# EKG_Modul_II.net
KiCad netlist of a schematic drawn in EAGLE
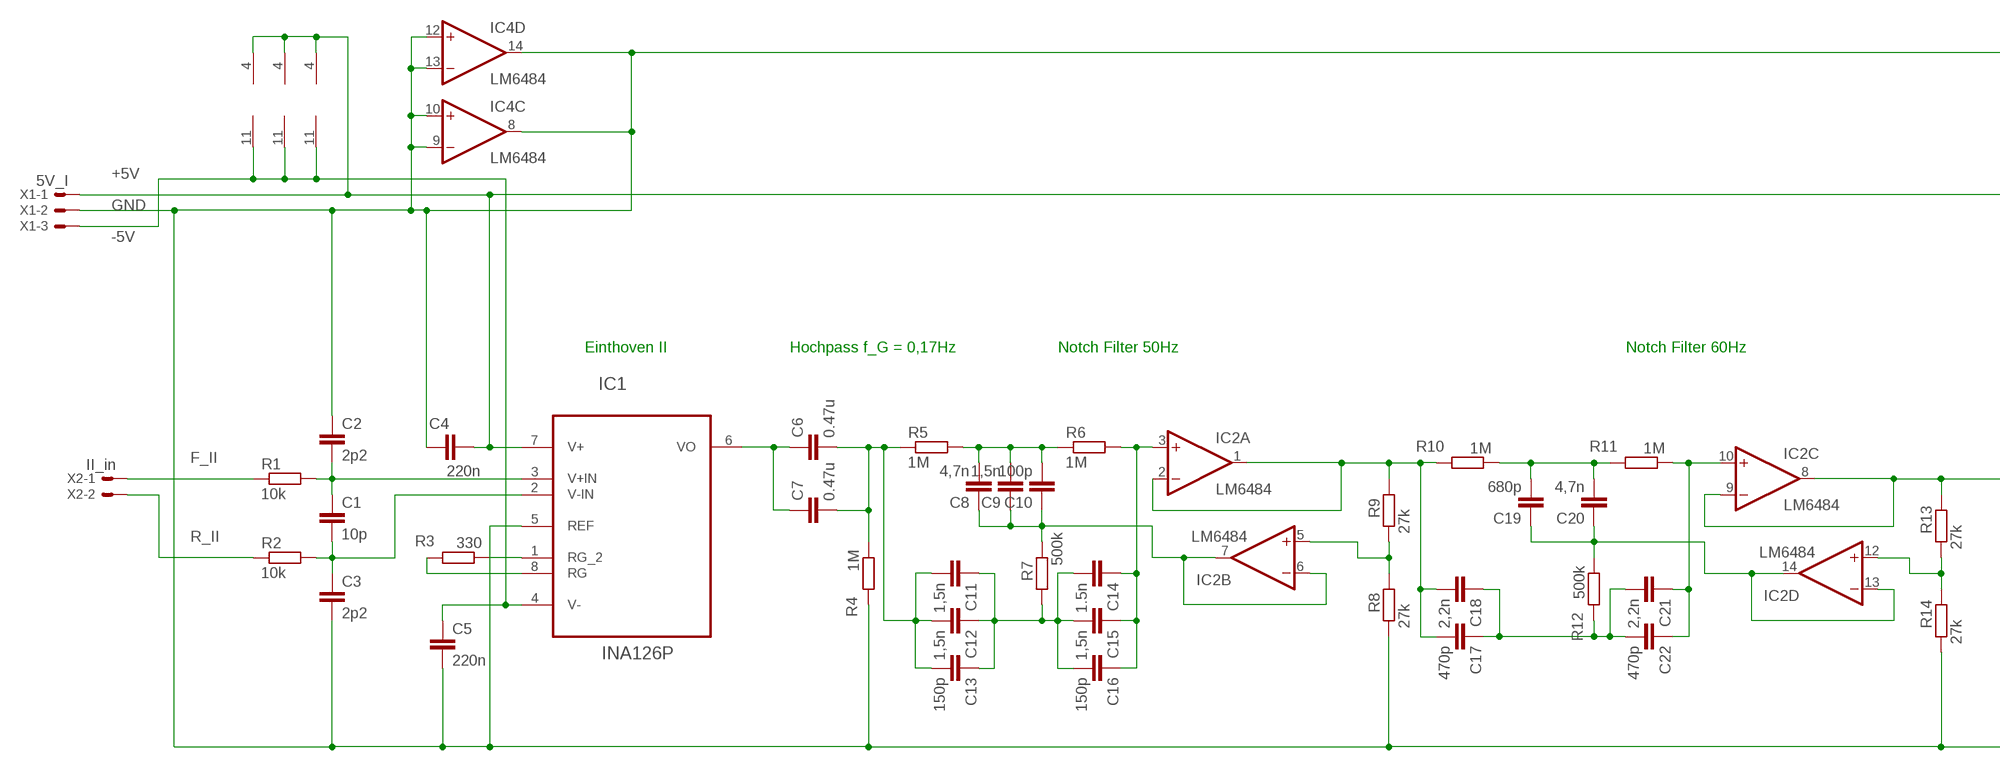
[diagram p0: schematic, sheet 1, part 1 of 2]
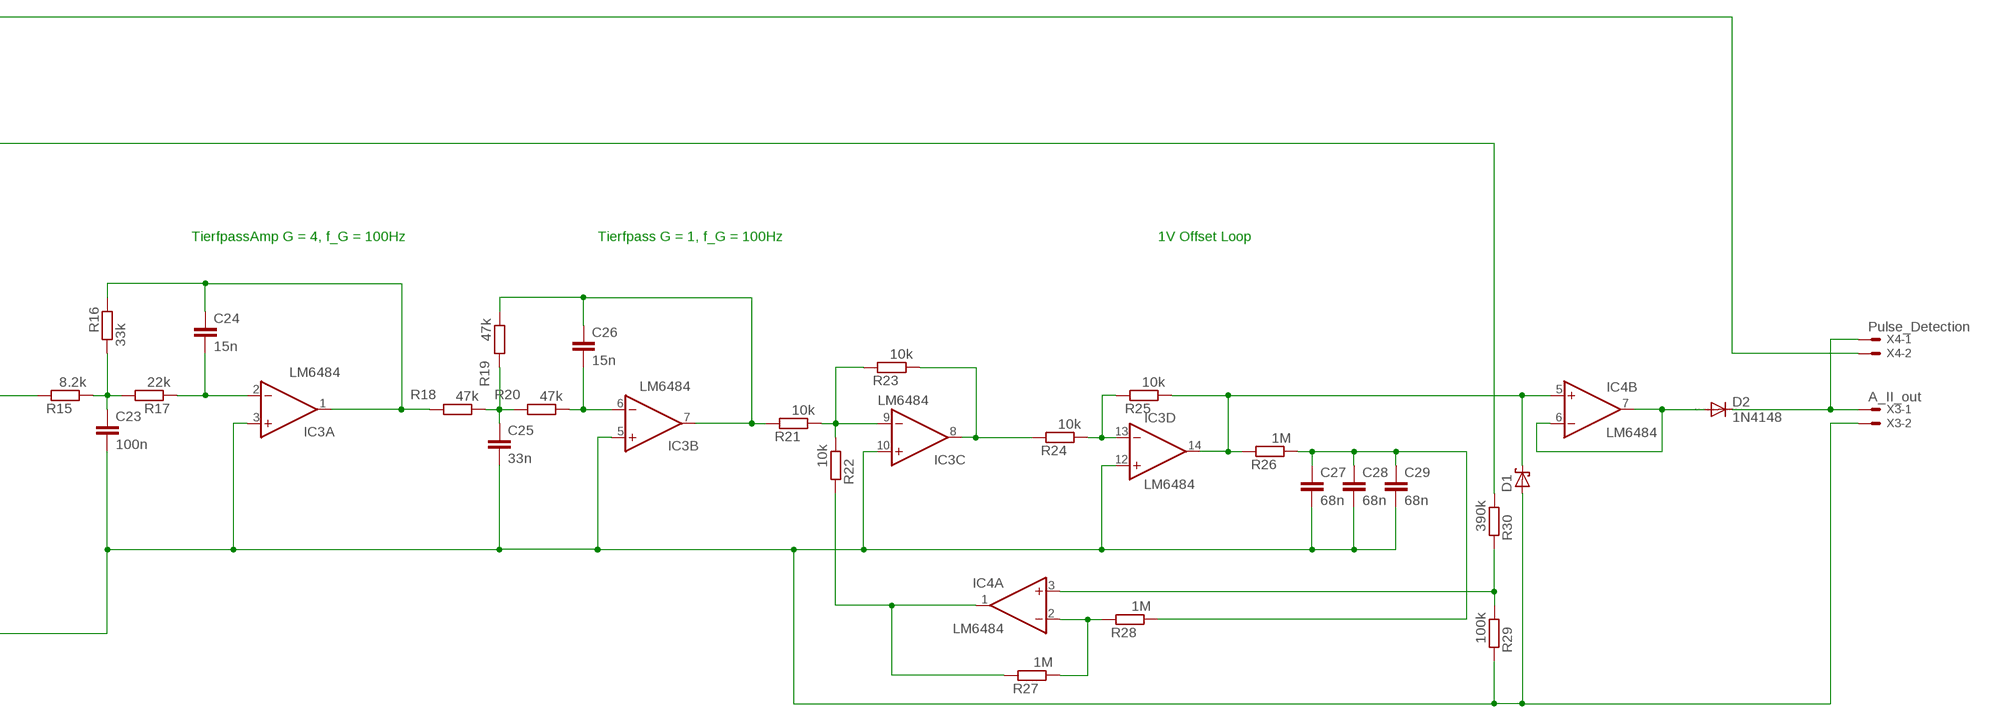
[diagram p1: schematic, sheet 1, part 2 of 2]

(export (version "E")
  (design (tool "Eeschema 10.0.6"))
  (components
    (comp (ref "C1")
      (value "10p")
      (footprint "eagle-import:C2.5-2")
      (libsource (lib "eagle-import") (part "C2.5/2"))
    )
    (comp (ref "C2")
      (value "2p2")
      (footprint "eagle-import:C2.5-2")
      (libsource (lib "eagle-import") (part "C2.5/2"))
    )
    (comp (ref "C3")
      (value "2p2")
      (footprint "eagle-import:C2.5-2")
      (libsource (lib "eagle-import") (part "C2.5/2"))
    )
    (comp (ref "C4")
      (value "220n")
      (footprint "eagle-import:C2.5-2")
      (libsource (lib "eagle-import") (part "C2.5/2"))
    )
    (comp (ref "C5")
      (value "220n")
      (footprint "eagle-import:C2.5-2")
      (libsource (lib "eagle-import") (part "C2.5/2"))
    )
    (comp (ref "C6")
      (value "0.47u")
      (footprint "eagle-import:C15B5")
      (libsource (lib "eagle-import") (part "C15/5"))
    )
    (comp (ref "C7")
      (value "0.47u")
      (footprint "eagle-import:C15B5")
      (libsource (lib "eagle-import") (part "C15/5"))
    )
    (comp (ref "C8")
      (value "4,7n")
      (footprint "eagle-import:C2.5-2")
      (libsource (lib "eagle-import") (part "C2.5/2"))
    )
    (comp (ref "C9")
      (value "1,5n")
      (footprint "eagle-import:C2.5-2")
      (libsource (lib "eagle-import") (part "C2.5/2"))
    )
    (comp (ref "C10")
      (value "100p")
      (footprint "eagle-import:C2.5-2")
      (libsource (lib "eagle-import") (part "C2.5/2"))
    )
    (comp (ref "C11")
      (value "1,5n")
      (footprint "eagle-import:C2.5-2")
      (libsource (lib "eagle-import") (part "C2.5/2"))
    )
    (comp (ref "C12")
      (value "1,5n")
      (footprint "eagle-import:C2.5-2")
      (libsource (lib "eagle-import") (part "C2.5/2"))
    )
    (comp (ref "C13")
      (value "150p")
      (footprint "eagle-import:C2.5-2")
      (libsource (lib "eagle-import") (part "C2.5/2"))
    )
    (comp (ref "C14")
      (value "1.5n")
      (footprint "eagle-import:C2.5-2")
      (libsource (lib "eagle-import") (part "C2.5/2"))
    )
    (comp (ref "C15")
      (value "1,5n")
      (footprint "eagle-import:C2.5-2")
      (libsource (lib "eagle-import") (part "C2.5/2"))
    )
    (comp (ref "C16")
      (value "150p")
      (footprint "eagle-import:C2.5-2")
      (libsource (lib "eagle-import") (part "C2.5/2"))
    )
    (comp (ref "C17")
      (value "470p")
      (footprint "eagle-import:C2.5-2")
      (libsource (lib "eagle-import") (part "C2.5/2"))
    )
    (comp (ref "C18")
      (value "2,2n")
      (footprint "eagle-import:C2.5-2")
      (libsource (lib "eagle-import") (part "C2.5/2"))
    )
    (comp (ref "C19")
      (value "680p")
      (footprint "eagle-import:C2.5-2")
      (libsource (lib "eagle-import") (part "C2.5/2"))
    )
    (comp (ref "C20")
      (value "4,7n")
      (footprint "eagle-import:C2.5-2")
      (libsource (lib "eagle-import") (part "C2.5/2"))
    )
    (comp (ref "C21")
      (value "2,2n")
      (footprint "eagle-import:C2.5-2")
      (libsource (lib "eagle-import") (part "C2.5/2"))
    )
    (comp (ref "C22")
      (value "470p")
      (footprint "eagle-import:C2.5-2")
      (libsource (lib "eagle-import") (part "C2.5/2"))
    )
    (comp (ref "C23")
      (value "100n")
      (footprint "eagle-import:C2.5-2")
      (libsource (lib "eagle-import") (part "C2.5/2"))
    )
    (comp (ref "C24")
      (value "15n")
      (footprint "eagle-import:C2.5-2")
      (libsource (lib "eagle-import") (part "C2.5/2"))
    )
    (comp (ref "C25")
      (value "33n")
      (footprint "eagle-import:C2.5-2")
      (libsource (lib "eagle-import") (part "C2.5/2"))
    )
    (comp (ref "C26")
      (value "15n")
      (footprint "eagle-import:C2.5-2")
      (libsource (lib "eagle-import") (part "C2.5/2"))
    )
    (comp (ref "C27")
      (value "68n")
      (footprint "eagle-import:C2.5-2")
      (libsource (lib "eagle-import") (part "C2.5/2"))
    )
    (comp (ref "C28")
      (value "68n")
      (footprint "eagle-import:C2.5-2")
      (libsource (lib "eagle-import") (part "C2.5/2"))
    )
    (comp (ref "C29")
      (value "68n")
      (footprint "eagle-import:C2.5-2")
      (libsource (lib "eagle-import") (part "C2.5/2"))
    )
    (comp (ref "D1")
      (value "SCHOTTKY-DIODEDO35-7")
      (footprint "eagle-import:DO35-7")
      (libsource (lib "eagle-import") (part "SCHOTTKY-DIODEDO35-7"))
    )
    (comp (ref "D2")
      (value "1N4148")
      (footprint "eagle-import:DO35-7")
      (libsource (lib "eagle-import") (part "1N4148DO35-7"))
    )
    (comp (ref "IC1")
      (value "INA126P")
      (footprint "eagle-import:DIP254P762X508-8")
      (fields (field (name "MF") "Texas Instruments"))
      (libsource (lib "eagle-import") (part "INA126P"))
    )
    (comp (ref "IC2")
      (value "LM6484")
      (footprint "eagle-import:DIL14")
      (libsource (lib "eagle-import") (part "QUAD_OPAMPP"))
    )
    (comp (ref "IC3")
      (value "LM6484")
      (footprint "eagle-import:DIL14")
      (libsource (lib "eagle-import") (part "QUAD_OPAMPP"))
    )
    (comp (ref "IC4")
      (value "LM6484")
      (footprint "eagle-import:DIL14")
      (libsource (lib "eagle-import") (part "QUAD_OPAMPP"))
    )
    (comp (ref "R1")
      (value "10k")
      (footprint "eagle-import:0207_7")
      (libsource (lib "eagle-import") (part "R-EU_0207/7"))
    )
    (comp (ref "R2")
      (value "10k")
      (footprint "eagle-import:0207_7")
      (libsource (lib "eagle-import") (part "R-EU_0207/7"))
    )
    (comp (ref "R3")
      (value "330")
      (footprint "eagle-import:0207_7")
      (libsource (lib "eagle-import") (part "R-EU_0207/7"))
    )
    (comp (ref "R4")
      (value "1M")
      (footprint "eagle-import:0207_7")
      (libsource (lib "eagle-import") (part "R-EU_0207/7"))
    )
    (comp (ref "R5")
      (value "1M")
      (footprint "eagle-import:0207_7")
      (libsource (lib "eagle-import") (part "R-EU_0207/7"))
    )
    (comp (ref "R6")
      (value "1M")
      (footprint "eagle-import:0207_7")
      (libsource (lib "eagle-import") (part "R-EU_0207/7"))
    )
    (comp (ref "R7")
      (value "500k")
      (footprint "eagle-import:0207_7")
      (libsource (lib "eagle-import") (part "R-EU_0207/7"))
    )
    (comp (ref "R8")
      (value "27k")
      (footprint "eagle-import:0207_7")
      (libsource (lib "eagle-import") (part "R-EU_0207/7"))
    )
    (comp (ref "R9")
      (value "27k")
      (footprint "eagle-import:0207_7")
      (libsource (lib "eagle-import") (part "R-EU_0207/7"))
    )
    (comp (ref "R10")
      (value "1M")
      (footprint "eagle-import:0207_7")
      (libsource (lib "eagle-import") (part "R-EU_0207/7"))
    )
    (comp (ref "R11")
      (value "1M")
      (footprint "eagle-import:0207_7")
      (libsource (lib "eagle-import") (part "R-EU_0207/7"))
    )
    (comp (ref "R12")
      (value "500k")
      (footprint "eagle-import:0207_7")
      (libsource (lib "eagle-import") (part "R-EU_0207/7"))
    )
    (comp (ref "R13")
      (value "27k")
      (footprint "eagle-import:0207_7")
      (libsource (lib "eagle-import") (part "R-EU_0207/7"))
    )
    (comp (ref "R14")
      (value "27k")
      (footprint "eagle-import:0207_7")
      (libsource (lib "eagle-import") (part "R-EU_0207/7"))
    )
    (comp (ref "R15")
      (value "8.2k")
      (footprint "eagle-import:0207_7")
      (libsource (lib "eagle-import") (part "R-EU_0207/7"))
    )
    (comp (ref "R16")
      (value "33k")
      (footprint "eagle-import:0207_7")
      (libsource (lib "eagle-import") (part "R-EU_0207/7"))
    )
    (comp (ref "R17")
      (value "22k")
      (footprint "eagle-import:0207_7")
      (libsource (lib "eagle-import") (part "R-EU_0207/7"))
    )
    (comp (ref "R18")
      (value "47k")
      (footprint "eagle-import:0207_7")
      (libsource (lib "eagle-import") (part "R-EU_0207/7"))
    )
    (comp (ref "R19")
      (value "47k")
      (footprint "eagle-import:0207_7")
      (libsource (lib "eagle-import") (part "R-EU_0207/7"))
    )
    (comp (ref "R20")
      (value "47k")
      (footprint "eagle-import:0207_7")
      (libsource (lib "eagle-import") (part "R-EU_0207/7"))
    )
    (comp (ref "R21")
      (value "10k")
      (footprint "eagle-import:0207_7")
      (libsource (lib "eagle-import") (part "R-EU_0207/7"))
    )
    (comp (ref "R22")
      (value "10k")
      (footprint "eagle-import:0207_7")
      (libsource (lib "eagle-import") (part "R-EU_0207/7"))
    )
    (comp (ref "R23")
      (value "10k")
      (footprint "eagle-import:0207_7")
      (libsource (lib "eagle-import") (part "R-EU_0207/7"))
    )
    (comp (ref "R24")
      (value "10k")
      (footprint "eagle-import:0207_7")
      (libsource (lib "eagle-import") (part "R-EU_0207/7"))
    )
    (comp (ref "R25")
      (value "10k")
      (footprint "eagle-import:0207_7")
      (libsource (lib "eagle-import") (part "R-EU_0207/7"))
    )
    (comp (ref "R26")
      (value "1M")
      (footprint "eagle-import:0207_7")
      (libsource (lib "eagle-import") (part "R-EU_0207/7"))
    )
    (comp (ref "R27")
      (value "1M")
      (footprint "eagle-import:0207_7")
      (libsource (lib "eagle-import") (part "R-EU_0207/7"))
    )
    (comp (ref "R28")
      (value "1M")
      (footprint "eagle-import:0207_7")
      (libsource (lib "eagle-import") (part "R-EU_0207/7"))
    )
    (comp (ref "R29")
      (value "100k")
      (footprint "eagle-import:0207_7")
      (libsource (lib "eagle-import") (part "R-EU_0207/7"))
    )
    (comp (ref "R30")
      (value "390k")
      (footprint "eagle-import:0207_7")
      (libsource (lib "eagle-import") (part "R-EU_0207/7"))
    )
    (comp (ref "X1")
      (value "5V_I")
      (footprint "eagle-import:JST-XH-03-PACKAGE-LONG-PAD")
      (libsource (lib "eagle-import") (part "JST-XH-03-PIN-LONG-PAD"))
    )
    (comp (ref "X2")
      (value "II_in")
      (footprint "eagle-import:JST-XH-02-PACKAGE-LONG-PAD")
      (libsource (lib "eagle-import") (part "JST-XH-02-PIN-LONG-PAD"))
    )
    (comp (ref "X3")
      (value "A_II_out")
      (footprint "eagle-import:JST-XH-02-PACKAGE-LONG-PAD")
      (libsource (lib "eagle-import") (part "JST-XH-02-PIN-LONG-PAD"))
    )
    (comp (ref "X4")
      (value "Pulse_Detection")
      (footprint "eagle-import:JST-XH-02-PACKAGE-LONG-PAD")
      (libsource (lib "eagle-import") (part "JST-XH-02-PIN-LONG-PAD"))
    )
  )
  (nets
    (net (code "1") (name "/+5V") (class "Default")
      (node (ref "C4") (pin "2") (pinfunction "2_2") (pintype "passive"))
      (node (ref "IC1") (pin "7") (pinfunction "V+_7") (pintype "power_in"))
      (node (ref "IC2") (pin "4") (pinfunction "V+_4") (pintype "power_in"))
      (node (ref "IC3") (pin "4") (pinfunction "V+_4") (pintype "power_in"))
      (node (ref "IC4") (pin "4") (pinfunction "V+_4") (pintype "power_in"))
      (node (ref "R30") (pin "1") (pinfunction "1_1") (pintype "passive"))
      (node (ref "X1") (pin "1") (pinfunction "S_1") (pintype "passive"))
    )
    (net (code "2") (name "/-5V") (class "Default")
      (node (ref "C5") (pin "1") (pinfunction "1_1") (pintype "passive"))
      (node (ref "IC1") (pin "4") (pinfunction "V-_4") (pintype "power_in"))
      (node (ref "IC2") (pin "11") (pinfunction "V-_11") (pintype "power_in"))
      (node (ref "IC3") (pin "11") (pinfunction "V-_11") (pintype "power_in"))
      (node (ref "IC4") (pin "11") (pinfunction "V-_11") (pintype "power_in"))
      (node (ref "X1") (pin "3") (pinfunction "S_3") (pintype "passive"))
    )
    (net (code "3") (name "/F_II") (class "Default")
      (node (ref "R1") (pin "1") (pinfunction "1_1") (pintype "passive"))
      (node (ref "X2") (pin "1") (pinfunction "S_1") (pintype "passive"))
    )
    (net (code "4") (name "/GND") (class "Default")
      (node (ref "C2") (pin "1") (pinfunction "1_1") (pintype "passive"))
      (node (ref "C23") (pin "2") (pinfunction "2_2") (pintype "passive"))
      (node (ref "C25") (pin "2") (pinfunction "2_2") (pintype "passive"))
      (node (ref "C27") (pin "2") (pinfunction "2_2") (pintype "passive"))
      (node (ref "C28") (pin "2") (pinfunction "2_2") (pintype "passive"))
      (node (ref "C29") (pin "2") (pinfunction "2_2") (pintype "passive"))
      (node (ref "C3") (pin "2") (pinfunction "2_2") (pintype "passive"))
      (node (ref "C4") (pin "1") (pinfunction "1_1") (pintype "passive"))
      (node (ref "C5") (pin "2") (pinfunction "2_2") (pintype "passive"))
      (node (ref "D1") (pin "A") (pinfunction "A_A") (pintype "passive"))
      (node (ref "IC1") (pin "5") (pinfunction "REF_5") (pintype "passive"))
      (node (ref "IC3") (pin "10") (pinfunction "+IN_10") (pintype "input"))
      (node (ref "IC3") (pin "12") (pinfunction "+IN_12") (pintype "input"))
      (node (ref "IC3") (pin "3") (pinfunction "+IN_3") (pintype "input"))
      (node (ref "IC3") (pin "5") (pinfunction "+IN_5") (pintype "input"))
      (node (ref "IC4") (pin "10") (pinfunction "+IN_10") (pintype "input"))
      (node (ref "IC4") (pin "12") (pinfunction "+IN_12") (pintype "input"))
      (node (ref "IC4") (pin "13") (pinfunction "-IN_13") (pintype "input"))
      (node (ref "IC4") (pin "14") (pinfunction "OUT_14") (pintype "output"))
      (node (ref "IC4") (pin "8") (pinfunction "OUT_8") (pintype "output"))
      (node (ref "IC4") (pin "9") (pinfunction "-IN_9") (pintype "input"))
      (node (ref "R14") (pin "1") (pinfunction "1_1") (pintype "passive"))
      (node (ref "R29") (pin "2") (pinfunction "2_2") (pintype "passive"))
      (node (ref "R4") (pin "2") (pinfunction "2_2") (pintype "passive"))
      (node (ref "R8") (pin "1") (pinfunction "1_1") (pintype "passive"))
      (node (ref "X1") (pin "2") (pinfunction "S_2") (pintype "passive"))
      (node (ref "X3") (pin "2") (pinfunction "S_2") (pintype "passive"))
      (node (ref "X4") (pin "2") (pinfunction "S_2") (pintype "passive"))
    )
    (net (code "5") (name "/R_II") (class "Default")
      (node (ref "R2") (pin "1") (pinfunction "1_1") (pintype "passive"))
      (node (ref "X2") (pin "2") (pinfunction "S_2") (pintype "passive"))
    )
    (net (code "6") (name "Net-(C10-Pad2)") (class "Default")
      (node (ref "C10") (pin "2") (pinfunction "2_2") (pintype "passive"))
      (node (ref "C8") (pin "2") (pinfunction "2_2") (pintype "passive"))
      (node (ref "C9") (pin "2") (pinfunction "2_2") (pintype "passive"))
      (node (ref "R5") (pin "2") (pinfunction "2_2") (pintype "passive"))
      (node (ref "R6") (pin "1") (pinfunction "1_1") (pintype "passive"))
    )
    (net (code "7") (name "Net-(C11-Pad1)") (class "Default")
      (node (ref "C11") (pin "1") (pinfunction "1_1") (pintype "passive"))
      (node (ref "C12") (pin "1") (pinfunction "1_1") (pintype "passive"))
      (node (ref "C13") (pin "1") (pinfunction "1_1") (pintype "passive"))
      (node (ref "C14") (pin "2") (pinfunction "2_2") (pintype "passive"))
      (node (ref "C15") (pin "2") (pinfunction "2_2") (pintype "passive"))
      (node (ref "C16") (pin "2") (pinfunction "2_2") (pintype "passive"))
      (node (ref "R7") (pin "1") (pinfunction "1_1") (pintype "passive"))
    )
    (net (code "8") (name "Net-(C11-Pad2)") (class "Default")
      (node (ref "C11") (pin "2") (pinfunction "2_2") (pintype "passive"))
      (node (ref "C12") (pin "2") (pinfunction "2_2") (pintype "passive"))
      (node (ref "C13") (pin "2") (pinfunction "2_2") (pintype "passive"))
      (node (ref "C6") (pin "2") (pinfunction "2_2") (pintype "passive"))
      (node (ref "C7") (pin "2") (pinfunction "2_2") (pintype "passive"))
      (node (ref "R4") (pin "1") (pinfunction "1_1") (pintype "passive"))
      (node (ref "R5") (pin "1") (pinfunction "1_1") (pintype "passive"))
    )
    (net (code "9") (name "Net-(C17-Pad1)") (class "Default")
      (node (ref "C17") (pin "1") (pinfunction "1_1") (pintype "passive"))
      (node (ref "C18") (pin "1") (pinfunction "1_1") (pintype "passive"))
      (node (ref "C21") (pin "2") (pinfunction "2_2") (pintype "passive"))
      (node (ref "C22") (pin "2") (pinfunction "2_2") (pintype "passive"))
      (node (ref "R12") (pin "2") (pinfunction "2_2") (pintype "passive"))
    )
    (net (code "10") (name "Net-(C19-Pad2)") (class "Default")
      (node (ref "C19") (pin "2") (pinfunction "2_2") (pintype "passive"))
      (node (ref "C20") (pin "2") (pinfunction "2_2") (pintype "passive"))
      (node (ref "R10") (pin "1") (pinfunction "1_1") (pintype "passive"))
      (node (ref "R11") (pin "2") (pinfunction "2_2") (pintype "passive"))
    )
    (net (code "11") (name "Net-(C23-Pad1)") (class "Default")
      (node (ref "C23") (pin "1") (pinfunction "1_1") (pintype "passive"))
      (node (ref "R15") (pin "1") (pinfunction "1_1") (pintype "passive"))
      (node (ref "R16") (pin "1") (pinfunction "1_1") (pintype "passive"))
      (node (ref "R17") (pin "2") (pinfunction "2_2") (pintype "passive"))
    )
    (net (code "12") (name "Net-(C25-Pad1)") (class "Default")
      (node (ref "C25") (pin "1") (pinfunction "1_1") (pintype "passive"))
      (node (ref "R18") (pin "1") (pinfunction "1_1") (pintype "passive"))
      (node (ref "R19") (pin "2") (pinfunction "2_2") (pintype "passive"))
      (node (ref "R20") (pin "2") (pinfunction "2_2") (pintype "passive"))
    )
    (net (code "13") (name "Net-(C27-Pad1)") (class "Default")
      (node (ref "C27") (pin "1") (pinfunction "1_1") (pintype "passive"))
      (node (ref "C28") (pin "1") (pinfunction "1_1") (pintype "passive"))
      (node (ref "C29") (pin "1") (pinfunction "1_1") (pintype "passive"))
      (node (ref "R26") (pin "1") (pinfunction "1_1") (pintype "passive"))
      (node (ref "R28") (pin "1") (pinfunction "1_1") (pintype "passive"))
    )
    (net (code "14") (name "Net-(IC1-RG)") (class "Default")
      (node (ref "IC1") (pin "8") (pinfunction "RG_8") (pintype "passive"))
      (node (ref "R3") (pin "2") (pinfunction "2_2") (pintype "passive"))
    )
    (net (code "15") (name "Net-(IC1-RG_2)") (class "Default")
      (node (ref "IC1") (pin "1") (pinfunction "RG_2_1") (pintype "passive"))
      (node (ref "R3") (pin "1") (pinfunction "1_1") (pintype "passive"))
    )
    (net (code "16") (name "Net-(IC1-V+IN)") (class "Default")
      (node (ref "C1") (pin "1") (pinfunction "1_1") (pintype "passive"))
      (node (ref "C2") (pin "2") (pinfunction "2_2") (pintype "passive"))
      (node (ref "IC1") (pin "3") (pinfunction "V+IN_3") (pintype "input"))
      (node (ref "R1") (pin "2") (pinfunction "2_2") (pintype "passive"))
    )
    (net (code "17") (name "Net-(IC1-V-IN)") (class "Default")
      (node (ref "C1") (pin "2") (pinfunction "2_2") (pintype "passive"))
      (node (ref "C3") (pin "1") (pinfunction "1_1") (pintype "passive"))
      (node (ref "IC1") (pin "2") (pinfunction "V-IN_2") (pintype "input"))
      (node (ref "R2") (pin "2") (pinfunction "2_2") (pintype "passive"))
    )
    (net (code "18") (name "Net-(IC1-VO)") (class "Default")
      (node (ref "C6") (pin "1") (pinfunction "1_1") (pintype "passive"))
      (node (ref "C7") (pin "1") (pinfunction "1_1") (pintype "passive"))
      (node (ref "IC1") (pin "6") (pinfunction "VO_6") (pintype "output"))
    )
    (net (code "19") (name "Net-(IC2A-+IN)") (class "Default")
      (node (ref "C14") (pin "1") (pinfunction "1_1") (pintype "passive"))
      (node (ref "C15") (pin "1") (pinfunction "1_1") (pintype "passive"))
      (node (ref "C16") (pin "1") (pinfunction "1_1") (pintype "passive"))
      (node (ref "IC2") (pin "3") (pinfunction "+IN_3") (pintype "input"))
      (node (ref "R6") (pin "2") (pinfunction "2_2") (pintype "passive"))
    )
    (net (code "20") (name "Net-(IC2A--IN)") (class "Default")
      (node (ref "C17") (pin "2") (pinfunction "2_2") (pintype "passive"))
      (node (ref "C18") (pin "2") (pinfunction "2_2") (pintype "passive"))
      (node (ref "IC2") (pin "1") (pinfunction "OUT_1") (pintype "output"))
      (node (ref "IC2") (pin "2") (pinfunction "-IN_2") (pintype "input"))
      (node (ref "R10") (pin "2") (pinfunction "2_2") (pintype "passive"))
      (node (ref "R9") (pin "2") (pinfunction "2_2") (pintype "passive"))
    )
    (net (code "21") (name "Net-(IC2B-+IN)") (class "Default")
      (node (ref "IC2") (pin "5") (pinfunction "+IN_5") (pintype "input"))
      (node (ref "R8") (pin "2") (pinfunction "2_2") (pintype "passive"))
      (node (ref "R9") (pin "1") (pinfunction "1_1") (pintype "passive"))
    )
    (net (code "22") (name "Net-(IC2B--IN)") (class "Default")
      (node (ref "C10") (pin "1") (pinfunction "1_1") (pintype "passive"))
      (node (ref "C8") (pin "1") (pinfunction "1_1") (pintype "passive"))
      (node (ref "C9") (pin "1") (pinfunction "1_1") (pintype "passive"))
      (node (ref "IC2") (pin "6") (pinfunction "-IN_6") (pintype "input"))
      (node (ref "IC2") (pin "7") (pinfunction "OUT_7") (pintype "output"))
      (node (ref "R7") (pin "2") (pinfunction "2_2") (pintype "passive"))
    )
    (net (code "23") (name "Net-(IC2C-+IN)") (class "Default")
      (node (ref "C21") (pin "1") (pinfunction "1_1") (pintype "passive"))
      (node (ref "C22") (pin "1") (pinfunction "1_1") (pintype "passive"))
      (node (ref "IC2") (pin "10") (pinfunction "+IN_10") (pintype "input"))
      (node (ref "R11") (pin "1") (pinfunction "1_1") (pintype "passive"))
    )
    (net (code "24") (name "Net-(IC2C--IN)") (class "Default")
      (node (ref "IC2") (pin "8") (pinfunction "OUT_8") (pintype "output"))
      (node (ref "IC2") (pin "9") (pinfunction "-IN_9") (pintype "input"))
      (node (ref "R13") (pin "2") (pinfunction "2_2") (pintype "passive"))
      (node (ref "R15") (pin "2") (pinfunction "2_2") (pintype "passive"))
    )
    (net (code "25") (name "Net-(IC2D-+IN)") (class "Default")
      (node (ref "IC2") (pin "12") (pinfunction "+IN_12") (pintype "input"))
      (node (ref "R13") (pin "1") (pinfunction "1_1") (pintype "passive"))
      (node (ref "R14") (pin "2") (pinfunction "2_2") (pintype "passive"))
    )
    (net (code "26") (name "Net-(IC2D--IN)") (class "Default")
      (node (ref "C19") (pin "1") (pinfunction "1_1") (pintype "passive"))
      (node (ref "C20") (pin "1") (pinfunction "1_1") (pintype "passive"))
      (node (ref "IC2") (pin "13") (pinfunction "-IN_13") (pintype "input"))
      (node (ref "IC2") (pin "14") (pinfunction "OUT_14") (pintype "output"))
      (node (ref "R12") (pin "1") (pinfunction "1_1") (pintype "passive"))
    )
    (net (code "27") (name "Net-(IC3A--IN)") (class "Default")
      (node (ref "C24") (pin "2") (pinfunction "2_2") (pintype "passive"))
      (node (ref "IC3") (pin "2") (pinfunction "-IN_2") (pintype "input"))
      (node (ref "R17") (pin "1") (pinfunction "1_1") (pintype "passive"))
    )
    (net (code "28") (name "Net-(IC3A-OUT)") (class "Default")
      (node (ref "C24") (pin "1") (pinfunction "1_1") (pintype "passive"))
      (node (ref "IC3") (pin "1") (pinfunction "OUT_1") (pintype "output"))
      (node (ref "R16") (pin "2") (pinfunction "2_2") (pintype "passive"))
      (node (ref "R18") (pin "2") (pinfunction "2_2") (pintype "passive"))
    )
    (net (code "29") (name "Net-(IC3B--IN)") (class "Default")
      (node (ref "C26") (pin "2") (pinfunction "2_2") (pintype "passive"))
      (node (ref "IC3") (pin "6") (pinfunction "-IN_6") (pintype "input"))
      (node (ref "R20") (pin "1") (pinfunction "1_1") (pintype "passive"))
    )
    (net (code "30") (name "Net-(IC3B-OUT)") (class "Default")
      (node (ref "C26") (pin "1") (pinfunction "1_1") (pintype "passive"))
      (node (ref "IC3") (pin "7") (pinfunction "OUT_7") (pintype "output"))
      (node (ref "R19") (pin "1") (pinfunction "1_1") (pintype "passive"))
      (node (ref "R21") (pin "2") (pinfunction "2_2") (pintype "passive"))
    )
    (net (code "31") (name "Net-(IC3C--IN)") (class "Default")
      (node (ref "IC3") (pin "9") (pinfunction "-IN_9") (pintype "input"))
      (node (ref "R21") (pin "1") (pinfunction "1_1") (pintype "passive"))
      (node (ref "R22") (pin "1") (pinfunction "1_1") (pintype "passive"))
      (node (ref "R23") (pin "2") (pinfunction "2_2") (pintype "passive"))
    )
    (net (code "32") (name "Net-(IC3C-OUT)") (class "Default")
      (node (ref "IC3") (pin "8") (pinfunction "OUT_8") (pintype "output"))
      (node (ref "R23") (pin "1") (pinfunction "1_1") (pintype "passive"))
      (node (ref "R24") (pin "2") (pinfunction "2_2") (pintype "passive"))
    )
    (net (code "33") (name "Net-(IC3D--IN)") (class "Default")
      (node (ref "IC3") (pin "13") (pinfunction "-IN_13") (pintype "input"))
      (node (ref "R24") (pin "1") (pinfunction "1_1") (pintype "passive"))
      (node (ref "R25") (pin "2") (pinfunction "2_2") (pintype "passive"))
    )
    (net (code "34") (name "Net-(IC3D-OUT)") (class "Default")
      (node (ref "D1") (pin "C") (pinfunction "C_C") (pintype "passive"))
      (node (ref "IC3") (pin "14") (pinfunction "OUT_14") (pintype "output"))
      (node (ref "IC4") (pin "5") (pinfunction "+IN_5") (pintype "input"))
      (node (ref "R25") (pin "1") (pinfunction "1_1") (pintype "passive"))
      (node (ref "R26") (pin "2") (pinfunction "2_2") (pintype "passive"))
    )
    (net (code "35") (name "Net-(IC4A-+IN)") (class "Default")
      (node (ref "IC4") (pin "3") (pinfunction "+IN_3") (pintype "input"))
      (node (ref "R29") (pin "1") (pinfunction "1_1") (pintype "passive"))
      (node (ref "R30") (pin "2") (pinfunction "2_2") (pintype "passive"))
    )
    (net (code "36") (name "Net-(IC4A--IN)") (class "Default")
      (node (ref "IC4") (pin "2") (pinfunction "-IN_2") (pintype "input"))
      (node (ref "R27") (pin "1") (pinfunction "1_1") (pintype "passive"))
      (node (ref "R28") (pin "2") (pinfunction "2_2") (pintype "passive"))
    )
    (net (code "37") (name "Net-(IC4A-OUT)") (class "Default")
      (node (ref "IC4") (pin "1") (pinfunction "OUT_1") (pintype "output"))
      (node (ref "R22") (pin "2") (pinfunction "2_2") (pintype "passive"))
      (node (ref "R27") (pin "2") (pinfunction "2_2") (pintype "passive"))
    )
    (net (code "38") (name "Net-(IC4B--IN)") (class "Default")
      (node (ref "D2") (pin "A") (pinfunction "A_A") (pintype "passive"))
      (node (ref "IC4") (pin "6") (pinfunction "-IN_6") (pintype "input"))
      (node (ref "IC4") (pin "7") (pinfunction "OUT_7") (pintype "output"))
    )
    (net (code "39") (name "Net-(X3A-S)") (class "Default")
      (node (ref "D2") (pin "C") (pinfunction "C_C") (pintype "passive"))
      (node (ref "X3") (pin "1") (pinfunction "S_1") (pintype "passive"))
      (node (ref "X4") (pin "1") (pinfunction "S_1") (pintype "passive"))
    )
  )
)
